# SteeringWheel.net
KiCad netlist of a schematic drawn in EAGLE
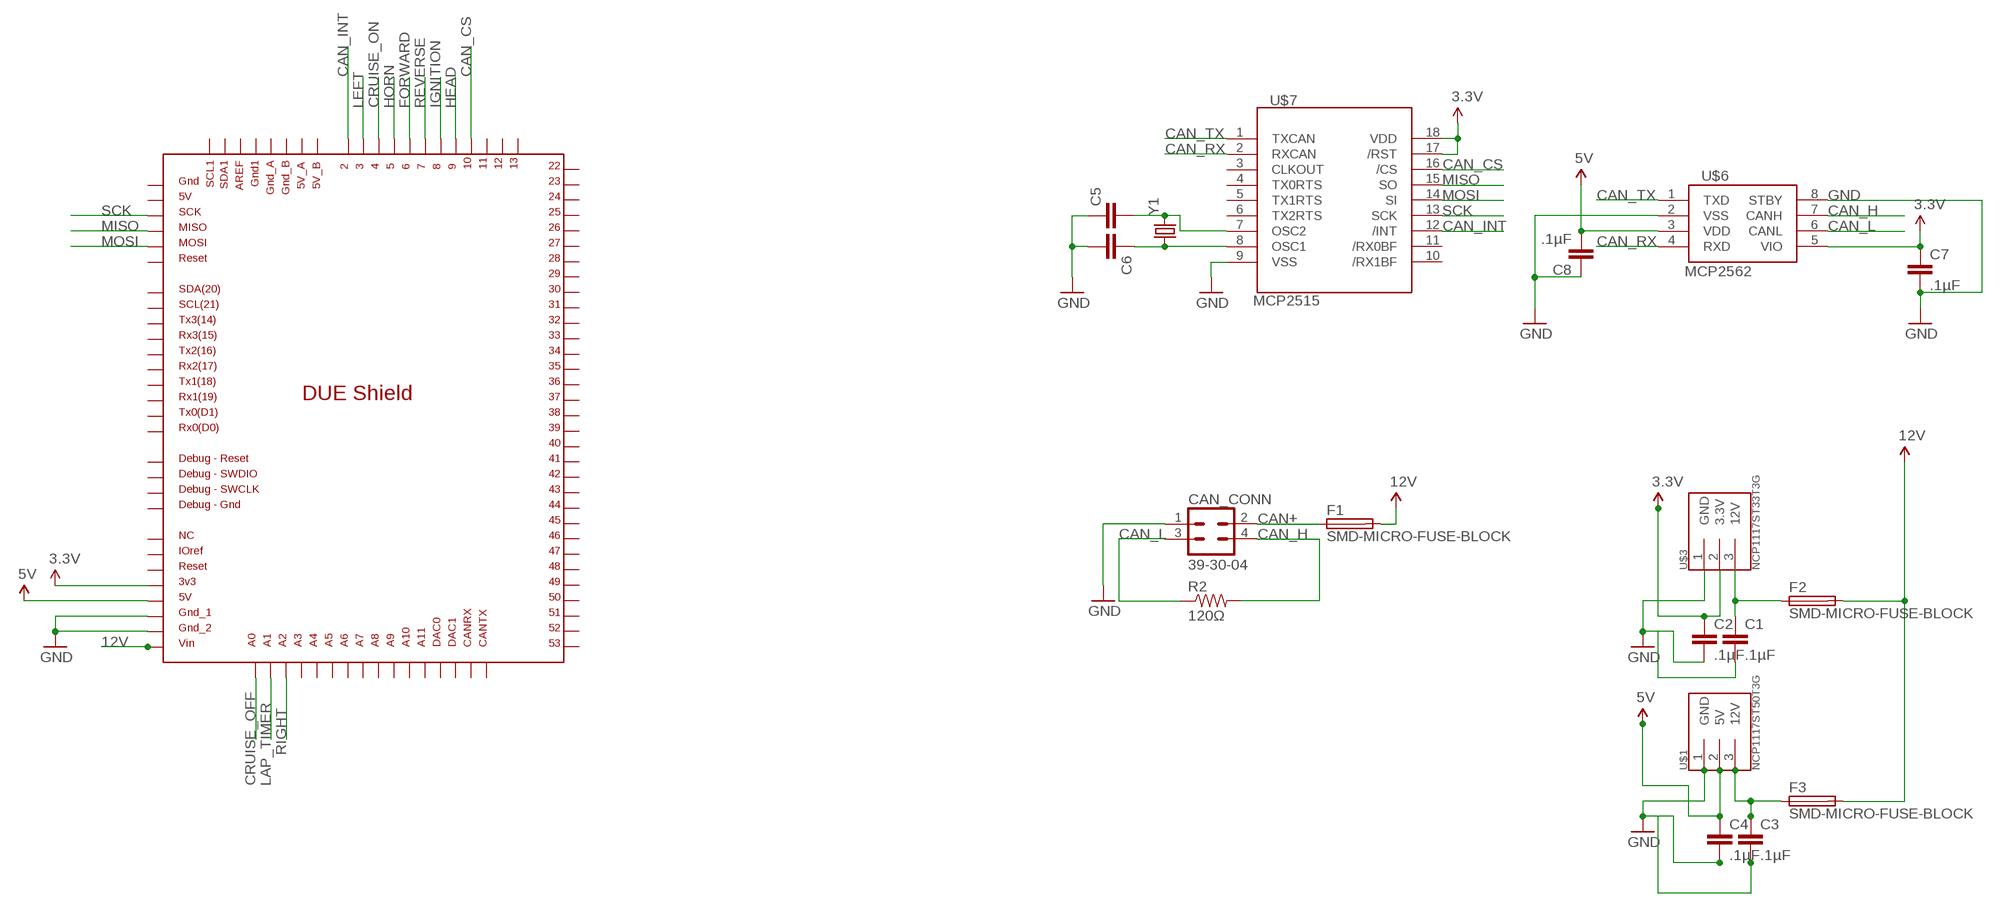
[diagram p0: schematic, sheet 1]

(export (version "E")
  (design (tool "Eeschema 10.0.6"))
  (components
    (comp (ref "C1")
      (value ".1µF")
      (footprint "eagle-import:0805")
      (libsource (lib "eagle-import") (part "CAP0805"))
    )
    (comp (ref "C2")
      (value ".1µF")
      (footprint "eagle-import:0805")
      (libsource (lib "eagle-import") (part "CAP0805"))
    )
    (comp (ref "C3")
      (value ".1µF")
      (footprint "eagle-import:0805")
      (libsource (lib "eagle-import") (part "CAP0805"))
    )
    (comp (ref "C4")
      (value ".1µF")
      (footprint "eagle-import:0805")
      (libsource (lib "eagle-import") (part "CAP0805"))
    )
    (comp (ref "C5")
      (value "CAP0805")
      (footprint "eagle-import:0805")
      (libsource (lib "eagle-import") (part "CAP0805"))
    )
    (comp (ref "C6")
      (value "CAP0805")
      (footprint "eagle-import:0805")
      (libsource (lib "eagle-import") (part "CAP0805"))
    )
    (comp (ref "C7")
      (value ".1µF")
      (footprint "eagle-import:0805")
      (libsource (lib "eagle-import") (part "CAP0805"))
    )
    (comp (ref "C8")
      (value ".1µF")
      (footprint "eagle-import:0805")
      (libsource (lib "eagle-import") (part "CAP0805"))
    )
    (comp (ref "CAN_CONN")
      (value "39-30-04")
      (footprint "eagle-import:39-30-_04_")
      (libsource (lib "eagle-import") (part "39-30-?04?"))
    )
    (comp (ref "F1")
      (value "SMD-MICRO-FUSE-BLOCK")
      (footprint "eagle-import:OMNIBLOK")
      (libsource (lib "eagle-import") (part "SMD-MICRO-FUSE-BLOCK"))
    )
    (comp (ref "F2")
      (value "SMD-MICRO-FUSE-BLOCK")
      (footprint "eagle-import:OMNIBLOK")
      (libsource (lib "eagle-import") (part "SMD-MICRO-FUSE-BLOCK"))
    )
    (comp (ref "F3")
      (value "SMD-MICRO-FUSE-BLOCK")
      (footprint "eagle-import:OMNIBLOK")
      (libsource (lib "eagle-import") (part "SMD-MICRO-FUSE-BLOCK"))
    )
    (comp (ref "R2")
      (value "120Ω")
      (footprint "eagle-import:0805")
      (libsource (lib "eagle-import") (part "RESISTOR0805-RES"))
    )
    (comp (ref "U$1")
      (value "NCP1117ST50T3G")
      (footprint "eagle-import:SOT223")
      (libsource (lib "eagle-import") (part "NCP1117ST50T3G"))
    )
    (comp (ref "U$2")
      (value "DUE(NORMAL)")
      (footprint "eagle-import:DUE(NORMAL)")
      (libsource (lib "eagle-import") (part "DUE(NORMAL)"))
    )
    (comp (ref "U$3")
      (value "NCP1117ST33T3G")
      (footprint "eagle-import:SOT223")
      (libsource (lib "eagle-import") (part "NCP1117ST33T3G"))
    )
    (comp (ref "U$6")
      (value "MCP2562")
      (footprint "eagle-import:SOIC8")
      (libsource (lib "eagle-import") (part "MCP2562"))
    )
    (comp (ref "U$7")
      (value "MCP2515")
      (footprint "eagle-import:SO-18W")
      (libsource (lib "eagle-import") (part "MCP2515"))
    )
    (comp (ref "Y1")
      (value "CRYSTALHC49US")
      (footprint "eagle-import:HC49US")
      (libsource (lib "eagle-import") (part "CRYSTALHC49US"))
    )
  )
  (nets
    (net (code "1") (name "/CAN+") (class "Default")
      (node (ref "CAN_CONN") (pin "2") (pinfunction "2_2") (pintype "passive"))
      (node (ref "F1") (pin "P$1") (pinfunction "1_P$1") (pintype "passive"))
    )
    (net (code "2") (name "/CAN_CS") (class "Default")
      (node (ref "U$2") (pin "10") (pinfunction "10_10") (pintype "bidirectional"))
      (node (ref "U$7") (pin "16") (pinfunction "/CS_16") (pintype "bidirectional"))
    )
    (net (code "3") (name "/CAN_H") (class "Default")
      (node (ref "CAN_CONN") (pin "4") (pinfunction "4_4") (pintype "passive"))
      (node (ref "R2") (pin "2") (pinfunction "2_2") (pintype "passive"))
      (node (ref "U$6") (pin "7") (pinfunction "CANH_7") (pintype "bidirectional"))
    )
    (net (code "4") (name "/CAN_INT") (class "Default")
      (node (ref "U$2") (pin "2") (pinfunction "2_2") (pintype "bidirectional"))
      (node (ref "U$7") (pin "12") (pinfunction "/INT_12") (pintype "bidirectional"))
    )
    (net (code "5") (name "/CAN_L") (class "Default")
      (node (ref "CAN_CONN") (pin "3") (pinfunction "3_3") (pintype "passive"))
      (node (ref "R2") (pin "1") (pinfunction "1_1") (pintype "passive"))
      (node (ref "U$6") (pin "6") (pinfunction "CANL_6") (pintype "bidirectional"))
    )
    (net (code "6") (name "/CAN_RX") (class "Default")
      (node (ref "U$6") (pin "4") (pinfunction "RXD_4") (pintype "bidirectional"))
      (node (ref "U$7") (pin "2") (pinfunction "RXCAN_2") (pintype "bidirectional"))
    )
    (net (code "7") (name "/CAN_TX") (class "Default")
      (node (ref "U$6") (pin "1") (pinfunction "TXD_1") (pintype "bidirectional"))
      (node (ref "U$7") (pin "1") (pinfunction "TXCAN_1") (pintype "bidirectional"))
    )
    (net (code "8") (name "/CRUISE_OFF") (class "Default")
      (node (ref "U$2") (pin "A0") (pinfunction "A0_A0") (pintype "bidirectional"))
    )
    (net (code "9") (name "/CRUISE_ON") (class "Default")
      (node (ref "U$2") (pin "4") (pinfunction "4_4") (pintype "bidirectional"))
    )
    (net (code "10") (name "/FORWARD") (class "Default")
      (node (ref "U$2") (pin "6") (pinfunction "6_6") (pintype "bidirectional"))
    )
    (net (code "11") (name "/HEAD") (class "Default")
      (node (ref "U$2") (pin "9") (pinfunction "9_9") (pintype "bidirectional"))
    )
    (net (code "12") (name "/HORN") (class "Default")
      (node (ref "U$2") (pin "5") (pinfunction "5_5") (pintype "bidirectional"))
    )
    (net (code "13") (name "/IGNITION") (class "Default")
      (node (ref "U$2") (pin "8") (pinfunction "8_8") (pintype "bidirectional"))
    )
    (net (code "14") (name "/LAP_TIMER") (class "Default")
      (node (ref "U$2") (pin "A1") (pinfunction "A1_A1") (pintype "bidirectional"))
    )
    (net (code "15") (name "/LEFT") (class "Default")
      (node (ref "U$2") (pin "3") (pinfunction "3_3") (pintype "bidirectional"))
    )
    (net (code "16") (name "/MISO") (class "Default")
      (node (ref "U$2") (pin "MISO_ICSP") (pinfunction "MISO_ICSP_MISO_ICSP") (pintype "bidirectional"))
      (node (ref "U$7") (pin "15") (pinfunction "SO_15") (pintype "bidirectional"))
    )
    (net (code "17") (name "/MOSI") (class "Default")
      (node (ref "U$2") (pin "MOSI_ICSP") (pinfunction "MOSI_ICSP_MOSI_ICSP") (pintype "bidirectional"))
      (node (ref "U$7") (pin "14") (pinfunction "SI_14") (pintype "bidirectional"))
    )
    (net (code "18") (name "/REVERSE") (class "Default")
      (node (ref "U$2") (pin "7") (pinfunction "7_7") (pintype "bidirectional"))
    )
    (net (code "19") (name "/RIGHT") (class "Default")
      (node (ref "U$2") (pin "A2") (pinfunction "A2_A2") (pintype "bidirectional"))
    )
    (net (code "20") (name "/SCK") (class "Default")
      (node (ref "U$2") (pin "SCK_ICSP") (pinfunction "SCK_ICSP_SCK_ICSP") (pintype "bidirectional"))
      (node (ref "U$7") (pin "13") (pinfunction "SCK_13") (pintype "bidirectional"))
    )
    (net (code "21") (name "3.3V") (class "Default")
      (node (ref "C2") (pin "1") (pinfunction "1_1") (pintype "passive"))
      (node (ref "C7") (pin "1") (pinfunction "1_1") (pintype "passive"))
      (node (ref "U$2") (pin "3V3") (pinfunction "3V3_3V3") (pintype "bidirectional"))
      (node (ref "U$3") (pin "2") (pinfunction "3.3V_2") (pintype "bidirectional"))
      (node (ref "U$6") (pin "5") (pinfunction "VIO_5") (pintype "bidirectional"))
      (node (ref "U$7") (pin "17") (pinfunction "/RST_17") (pintype "bidirectional"))
      (node (ref "U$7") (pin "18") (pinfunction "VDD_18") (pintype "bidirectional"))
    )
    (net (code "22") (name "5V") (class "Default")
      (node (ref "C4") (pin "1") (pinfunction "1_1") (pintype "passive"))
      (node (ref "C8") (pin "2") (pinfunction "2_2") (pintype "passive"))
      (node (ref "U$1") (pin "2") (pinfunction "5V_2") (pintype "bidirectional"))
      (node (ref "U$2") (pin "5V") (pinfunction "5V_5V") (pintype "bidirectional"))
      (node (ref "U$6") (pin "3") (pinfunction "VDD_3") (pintype "bidirectional"))
    )
    (net (code "23") (name "12V") (class "Default")
      (node (ref "F1") (pin "P$2") (pinfunction "2_P$2") (pintype "passive"))
      (node (ref "F2") (pin "P$2") (pinfunction "2_P$2") (pintype "passive"))
      (node (ref "F3") (pin "P$2") (pinfunction "2_P$2") (pintype "passive"))
      (node (ref "U$2") (pin "VIN") (pinfunction "VIN_VIN") (pintype "bidirectional"))
    )
    (net (code "24") (name "GND") (class "Default")
      (node (ref "C1") (pin "2") (pinfunction "2_2") (pintype "passive"))
      (node (ref "C2") (pin "2") (pinfunction "2_2") (pintype "passive"))
      (node (ref "C3") (pin "2") (pinfunction "2_2") (pintype "passive"))
      (node (ref "C4") (pin "2") (pinfunction "2_2") (pintype "passive"))
      (node (ref "C5") (pin "1") (pinfunction "1_1") (pintype "passive"))
      (node (ref "C6") (pin "2") (pinfunction "2_2") (pintype "passive"))
      (node (ref "C7") (pin "2") (pinfunction "2_2") (pintype "passive"))
      (node (ref "C8") (pin "1") (pinfunction "1_1") (pintype "passive"))
      (node (ref "CAN_CONN") (pin "1") (pinfunction "1_1") (pintype "passive"))
      (node (ref "U$1") (pin "1") (pinfunction "GND_1") (pintype "bidirectional"))
      (node (ref "U$2") (pin "GND_1") (pinfunction "GND_1_GND_1") (pintype "bidirectional"))
      (node (ref "U$2") (pin "GND_2") (pinfunction "GND_2_GND_2") (pintype "bidirectional"))
      (node (ref "U$3") (pin "1") (pinfunction "GND_1") (pintype "bidirectional"))
      (node (ref "U$6") (pin "2") (pinfunction "VSS_2") (pintype "bidirectional"))
      (node (ref "U$6") (pin "8") (pinfunction "STBY_8") (pintype "bidirectional"))
      (node (ref "U$7") (pin "9") (pinfunction "VSS_9") (pintype "bidirectional"))
    )
    (net (code "25") (name "Net-(F2-1)") (class "Default")
      (node (ref "C1") (pin "1") (pinfunction "1_1") (pintype "passive"))
      (node (ref "F2") (pin "P$1") (pinfunction "1_P$1") (pintype "passive"))
      (node (ref "U$3") (pin "3") (pinfunction "12V_3") (pintype "bidirectional"))
    )
    (net (code "26") (name "Net-(F3-1)") (class "Default")
      (node (ref "C3") (pin "1") (pinfunction "1_1") (pintype "passive"))
      (node (ref "F3") (pin "P$1") (pinfunction "1_P$1") (pintype "passive"))
      (node (ref "U$1") (pin "3") (pinfunction "12V_3") (pintype "bidirectional"))
    )
    (net (code "27") (name "Net-(U$7-OSC1)") (class "Default")
      (node (ref "C6") (pin "1") (pinfunction "1_1") (pintype "passive"))
      (node (ref "U$7") (pin "8") (pinfunction "OSC1_8") (pintype "bidirectional"))
      (node (ref "Y1") (pin "1") (pinfunction "1_1") (pintype "passive"))
    )
    (net (code "28") (name "Net-(U$7-OSC2)") (class "Default")
      (node (ref "C5") (pin "2") (pinfunction "2_2") (pintype "passive"))
      (node (ref "U$7") (pin "7") (pinfunction "OSC2_7") (pintype "bidirectional"))
      (node (ref "Y1") (pin "2") (pinfunction "2_2") (pintype "passive"))
    )
    (net (code "29") (name "unconnected-(U$2-Pad5V_A)") (class "Default")
      (node (ref "U$2") (pin "5V_A") (pinfunction "5V_A_5V_A") (pintype "bidirectional"))
    )
    (net (code "30") (name "unconnected-(U$2-Pad5V_B)") (class "Default")
      (node (ref "U$2") (pin "5V_B") (pinfunction "5V_B_5V_B") (pintype "bidirectional"))
    )
    (net (code "31") (name "unconnected-(U$2-Pad5V_ICSP)") (class "Default")
      (node (ref "U$2") (pin "5V_ICSP") (pinfunction "5V_ICSP_5V_ICSP") (pintype "bidirectional"))
    )
    (net (code "32") (name "unconnected-(U$2-Pad11)") (class "Default")
      (node (ref "U$2") (pin "11") (pinfunction "11_11") (pintype "bidirectional"))
    )
    (net (code "33") (name "unconnected-(U$2-Pad12)") (class "Default")
      (node (ref "U$2") (pin "12") (pinfunction "12_12") (pintype "bidirectional"))
    )
    (net (code "34") (name "unconnected-(U$2-Pad13)") (class "Default")
      (node (ref "U$2") (pin "13") (pinfunction "13_13") (pintype "bidirectional"))
    )
    (net (code "35") (name "unconnected-(U$2-Pad22)") (class "Default")
      (node (ref "U$2") (pin "22") (pinfunction "22_22") (pintype "bidirectional"))
    )
    (net (code "36") (name "unconnected-(U$2-Pad23)") (class "Default")
      (node (ref "U$2") (pin "23") (pinfunction "23_23") (pintype "bidirectional"))
    )
    (net (code "37") (name "unconnected-(U$2-Pad24)") (class "Default")
      (node (ref "U$2") (pin "24") (pinfunction "24_24") (pintype "bidirectional"))
    )
    (net (code "38") (name "unconnected-(U$2-Pad25)") (class "Default")
      (node (ref "U$2") (pin "25") (pinfunction "25_25") (pintype "bidirectional"))
    )
    (net (code "39") (name "unconnected-(U$2-Pad26)") (class "Default")
      (node (ref "U$2") (pin "26") (pinfunction "26_26") (pintype "bidirectional"))
    )
    (net (code "40") (name "unconnected-(U$2-Pad27)") (class "Default")
      (node (ref "U$2") (pin "27") (pinfunction "27_27") (pintype "bidirectional"))
    )
    (net (code "41") (name "unconnected-(U$2-Pad28)") (class "Default")
      (node (ref "U$2") (pin "28") (pinfunction "28_28") (pintype "bidirectional"))
    )
    (net (code "42") (name "unconnected-(U$2-Pad29)") (class "Default")
      (node (ref "U$2") (pin "29") (pinfunction "29_29") (pintype "bidirectional"))
    )
    (net (code "43") (name "unconnected-(U$2-Pad30)") (class "Default")
      (node (ref "U$2") (pin "30") (pinfunction "30_30") (pintype "bidirectional"))
    )
    (net (code "44") (name "unconnected-(U$2-Pad31)") (class "Default")
      (node (ref "U$2") (pin "31") (pinfunction "31_31") (pintype "bidirectional"))
    )
    (net (code "45") (name "unconnected-(U$2-Pad32)") (class "Default")
      (node (ref "U$2") (pin "32") (pinfunction "32_32") (pintype "bidirectional"))
    )
    (net (code "46") (name "unconnected-(U$2-Pad33)") (class "Default")
      (node (ref "U$2") (pin "33") (pinfunction "33_33") (pintype "bidirectional"))
    )
    (net (code "47") (name "unconnected-(U$2-Pad34)") (class "Default")
      (node (ref "U$2") (pin "34") (pinfunction "34_34") (pintype "bidirectional"))
    )
    (net (code "48") (name "unconnected-(U$2-Pad35)") (class "Default")
      (node (ref "U$2") (pin "35") (pinfunction "35_35") (pintype "bidirectional"))
    )
    (net (code "49") (name "unconnected-(U$2-Pad36)") (class "Default")
      (node (ref "U$2") (pin "36") (pinfunction "36_36") (pintype "bidirectional"))
    )
    (net (code "50") (name "unconnected-(U$2-Pad37)") (class "Default")
      (node (ref "U$2") (pin "37") (pinfunction "37_37") (pintype "bidirectional"))
    )
    (net (code "51") (name "unconnected-(U$2-Pad38)") (class "Default")
      (node (ref "U$2") (pin "38") (pinfunction "38_38") (pintype "bidirectional"))
    )
    (net (code "52") (name "unconnected-(U$2-Pad39)") (class "Default")
      (node (ref "U$2") (pin "39") (pinfunction "39_39") (pintype "bidirectional"))
    )
    (net (code "53") (name "unconnected-(U$2-Pad40)") (class "Default")
      (node (ref "U$2") (pin "40") (pinfunction "40_40") (pintype "bidirectional"))
    )
    (net (code "54") (name "unconnected-(U$2-Pad41)") (class "Default")
      (node (ref "U$2") (pin "41") (pinfunction "41_41") (pintype "bidirectional"))
    )
    (net (code "55") (name "unconnected-(U$2-Pad42)") (class "Default")
      (node (ref "U$2") (pin "42") (pinfunction "42_42") (pintype "bidirectional"))
    )
    (net (code "56") (name "unconnected-(U$2-Pad43)") (class "Default")
      (node (ref "U$2") (pin "43") (pinfunction "43_43") (pintype "bidirectional"))
    )
    (net (code "57") (name "unconnected-(U$2-Pad44)") (class "Default")
      (node (ref "U$2") (pin "44") (pinfunction "44_44") (pintype "bidirectional"))
    )
    (net (code "58") (name "unconnected-(U$2-Pad45)") (class "Default")
      (node (ref "U$2") (pin "45") (pinfunction "45_45") (pintype "bidirectional"))
    )
    (net (code "59") (name "unconnected-(U$2-Pad46)") (class "Default")
      (node (ref "U$2") (pin "46") (pinfunction "46_46") (pintype "bidirectional"))
    )
    (net (code "60") (name "unconnected-(U$2-Pad47)") (class "Default")
      (node (ref "U$2") (pin "47") (pinfunction "47_47") (pintype "bidirectional"))
    )
    (net (code "61") (name "unconnected-(U$2-Pad48)") (class "Default")
      (node (ref "U$2") (pin "48") (pinfunction "48_48") (pintype "bidirectional"))
    )
    (net (code "62") (name "unconnected-(U$2-Pad49)") (class "Default")
      (node (ref "U$2") (pin "49") (pinfunction "49_49") (pintype "bidirectional"))
    )
    (net (code "63") (name "unconnected-(U$2-Pad50)") (class "Default")
      (node (ref "U$2") (pin "50") (pinfunction "50_50") (pintype "bidirectional"))
    )
    (net (code "64") (name "unconnected-(U$2-Pad51)") (class "Default")
      (node (ref "U$2") (pin "51") (pinfunction "51_51") (pintype "bidirectional"))
    )
    (net (code "65") (name "unconnected-(U$2-Pad52)") (class "Default")
      (node (ref "U$2") (pin "52") (pinfunction "52_52") (pintype "bidirectional"))
    )
    (net (code "66") (name "unconnected-(U$2-Pad53)") (class "Default")
      (node (ref "U$2") (pin "53") (pinfunction "53_53") (pintype "bidirectional"))
    )
    (net (code "67") (name "unconnected-(U$2-PadA3)") (class "Default")
      (node (ref "U$2") (pin "A3") (pinfunction "A3_A3") (pintype "bidirectional"))
    )
    (net (code "68") (name "unconnected-(U$2-PadA4)") (class "Default")
      (node (ref "U$2") (pin "A4") (pinfunction "A4_A4") (pintype "bidirectional"))
    )
    (net (code "69") (name "unconnected-(U$2-PadA5)") (class "Default")
      (node (ref "U$2") (pin "A5") (pinfunction "A5_A5") (pintype "bidirectional"))
    )
    (net (code "70") (name "unconnected-(U$2-PadA6)") (class "Default")
      (node (ref "U$2") (pin "A6") (pinfunction "A6_A6") (pintype "bidirectional"))
    )
    (net (code "71") (name "unconnected-(U$2-PadA7)") (class "Default")
      (node (ref "U$2") (pin "A7") (pinfunction "A7_A7") (pintype "bidirectional"))
    )
    (net (code "72") (name "unconnected-(U$2-PadA8)") (class "Default")
      (node (ref "U$2") (pin "A8") (pinfunction "A8_A8") (pintype "bidirectional"))
    )
    (net (code "73") (name "unconnected-(U$2-PadA9)") (class "Default")
      (node (ref "U$2") (pin "A9") (pinfunction "A9_A9") (pintype "bidirectional"))
    )
    (net (code "74") (name "unconnected-(U$2-PadA10)") (class "Default")
      (node (ref "U$2") (pin "A10") (pinfunction "A10_A10") (pintype "bidirectional"))
    )
    (net (code "75") (name "unconnected-(U$2-PadA11)") (class "Default")
      (node (ref "U$2") (pin "A11") (pinfunction "A11_A11") (pintype "bidirectional"))
    )
    (net (code "76") (name "unconnected-(U$2-PadAREF)") (class "Default")
      (node (ref "U$2") (pin "AREF") (pinfunction "AREF_AREF") (pintype "bidirectional"))
    )
    (net (code "77") (name "unconnected-(U$2-PadCANRX)") (class "Default")
      (node (ref "U$2") (pin "CANRX") (pinfunction "CANRX_CANRX") (pintype "bidirectional"))
    )
    (net (code "78") (name "unconnected-(U$2-PadCANTX)") (class "Default")
      (node (ref "U$2") (pin "CANTX") (pinfunction "CANTX_CANTX") (pintype "bidirectional"))
    )
    (net (code "79") (name "unconnected-(U$2-PadDAC0)") (class "Default")
      (node (ref "U$2") (pin "DAC0") (pinfunction "DAC0_DAC0") (pintype "bidirectional"))
    )
    (net (code "80") (name "unconnected-(U$2-PadDAC1)") (class "Default")
      (node (ref "U$2") (pin "DAC1") (pinfunction "DAC1_DAC1") (pintype "bidirectional"))
    )
    (net (code "81") (name "unconnected-(U$2-PadGND1)") (class "Default")
      (node (ref "U$2") (pin "GND1") (pinfunction "GND1_GND1") (pintype "bidirectional"))
    )
    (net (code "82") (name "unconnected-(U$2-PadGND_A)") (class "Default")
      (node (ref "U$2") (pin "GND_A") (pinfunction "GND_A_GND_A") (pintype "bidirectional"))
    )
    (net (code "83") (name "unconnected-(U$2-PadGND_B)") (class "Default")
      (node (ref "U$2") (pin "GND_B") (pinfunction "GND_B_GND_B") (pintype "bidirectional"))
    )
    (net (code "84") (name "unconnected-(U$2-PadGND_DEBUG)") (class "Default")
      (node (ref "U$2") (pin "GND_DEBUG") (pinfunction "GND_DEBUG_GND_DEBUG") (pintype "bidirectional"))
    )
    (net (code "85") (name "unconnected-(U$2-PadGND_ICSP)") (class "Default")
      (node (ref "U$2") (pin "GND_ICSP") (pinfunction "GND_ICSP_GND_ICSP") (pintype "bidirectional"))
    )
    (net (code "86") (name "unconnected-(U$2-PadIOREF)") (class "Default")
      (node (ref "U$2") (pin "IOREF") (pinfunction "IOREF_IOREF") (pintype "bidirectional"))
    )
    (net (code "87") (name "unconnected-(U$2-PadNC)") (class "Default")
      (node (ref "U$2") (pin "NC") (pinfunction "NC_NC") (pintype "bidirectional"))
    )
    (net (code "88") (name "unconnected-(U$2-PadRESET)") (class "Default")
      (node (ref "U$2") (pin "RESET") (pinfunction "RESET_RESET") (pintype "bidirectional"))
    )
    (net (code "89") (name "unconnected-(U$2-PadRESET_DEBUG)") (class "Default")
      (node (ref "U$2") (pin "RESET_DEBUG") (pinfunction "RESET_DEBUG_RESET_DEBUG") (pintype "bidirectional"))
    )
    (net (code "90") (name "unconnected-(U$2-PadRESET_ICSP)") (class "Default")
      (node (ref "U$2") (pin "RESET_ICSP") (pinfunction "RESET_ICSP_RESET_ICSP") (pintype "bidirectional"))
    )
    (net (code "91") (name "unconnected-(U$2-PadRX0)") (class "Default")
      (node (ref "U$2") (pin "RX0") (pinfunction "RX0_RX0") (pintype "bidirectional"))
    )
    (net (code "92") (name "unconnected-(U$2-PadRX1)") (class "Default")
      (node (ref "U$2") (pin "RX1") (pinfunction "RX1_RX1") (pintype "bidirectional"))
    )
    (net (code "93") (name "unconnected-(U$2-PadRX2)") (class "Default")
      (node (ref "U$2") (pin "RX2") (pinfunction "RX2_RX2") (pintype "bidirectional"))
    )
    (net (code "94") (name "unconnected-(U$2-PadRX3)") (class "Default")
      (node (ref "U$2") (pin "RX3") (pinfunction "RX3_RX3") (pintype "bidirectional"))
    )
    (net (code "95") (name "unconnected-(U$2-PadSCL)") (class "Default")
      (node (ref "U$2") (pin "SCL") (pinfunction "SCL_SCL") (pintype "bidirectional"))
    )
    (net (code "96") (name "unconnected-(U$2-PadSCL1)") (class "Default")
      (node (ref "U$2") (pin "SCL1") (pinfunction "SCL1_SCL1") (pintype "bidirectional"))
    )
    (net (code "97") (name "unconnected-(U$2-PadSDA)") (class "Default")
      (node (ref "U$2") (pin "SDA") (pinfunction "SDA_SDA") (pintype "bidirectional"))
    )
    (net (code "98") (name "unconnected-(U$2-PadSDA1)") (class "Default")
      (node (ref "U$2") (pin "SDA1") (pinfunction "SDA1_SDA1") (pintype "bidirectional"))
    )
    (net (code "99") (name "unconnected-(U$2-PadSWCLK_DEBUG)") (class "Default")
      (node (ref "U$2") (pin "SWCLK_DEBUG") (pinfunction "SWCLK_DEBUG_SWCLK_DEBUG") (pintype "bidirectional"))
    )
    (net (code "100") (name "unconnected-(U$2-PadSWDIO_DEBUG)") (class "Default")
      (node (ref "U$2") (pin "SWDIO_DEBUG") (pinfunction "SWDIO_DEBUG_SWDIO_DEBUG") (pintype "bidirectional"))
    )
    (net (code "101") (name "unconnected-(U$2-PadTX0)") (class "Default")
      (node (ref "U$2") (pin "TX0") (pinfunction "TX0_TX0") (pintype "bidirectional"))
    )
    (net (code "102") (name "unconnected-(U$2-PadTX1)") (class "Default")
      (node (ref "U$2") (pin "TX1") (pinfunction "TX1_TX1") (pintype "bidirectional"))
    )
    (net (code "103") (name "unconnected-(U$2-PadTX2)") (class "Default")
      (node (ref "U$2") (pin "TX2") (pinfunction "TX2_TX2") (pintype "bidirectional"))
    )
    (net (code "104") (name "unconnected-(U$2-PadTX3)") (class "Default")
      (node (ref "U$2") (pin "TX3") (pinfunction "TX3_TX3") (pintype "bidirectional"))
    )
    (net (code "105") (name "unconnected-(U$7-CLKOUT-Pad3)") (class "Default")
      (node (ref "U$7") (pin "3") (pinfunction "CLKOUT_3") (pintype "bidirectional"))
    )
    (net (code "106") (name "unconnected-(U$7-TX0RTS-Pad4)") (class "Default")
      (node (ref "U$7") (pin "4") (pinfunction "TX0RTS_4") (pintype "bidirectional"))
    )
    (net (code "107") (name "unconnected-(U$7-TX1RTS-Pad5)") (class "Default")
      (node (ref "U$7") (pin "5") (pinfunction "TX1RTS_5") (pintype "bidirectional"))
    )
    (net (code "108") (name "unconnected-(U$7-TX2RTS-Pad6)") (class "Default")
      (node (ref "U$7") (pin "6") (pinfunction "TX2RTS_6") (pintype "bidirectional"))
    )
    (net (code "109") (name "unconnected-(U$7-{slash}RX0BF-Pad11)") (class "Default")
      (node (ref "U$7") (pin "11") (pinfunction "/RX0BF_11") (pintype "bidirectional"))
    )
    (net (code "110") (name "unconnected-(U$7-{slash}RX1BF-Pad10)") (class "Default")
      (node (ref "U$7") (pin "10") (pinfunction "/RX1BF_10") (pintype "bidirectional"))
    )
  )
)
